# PRegulator.net
KiCad netlist of a schematic drawn in Altium Designer
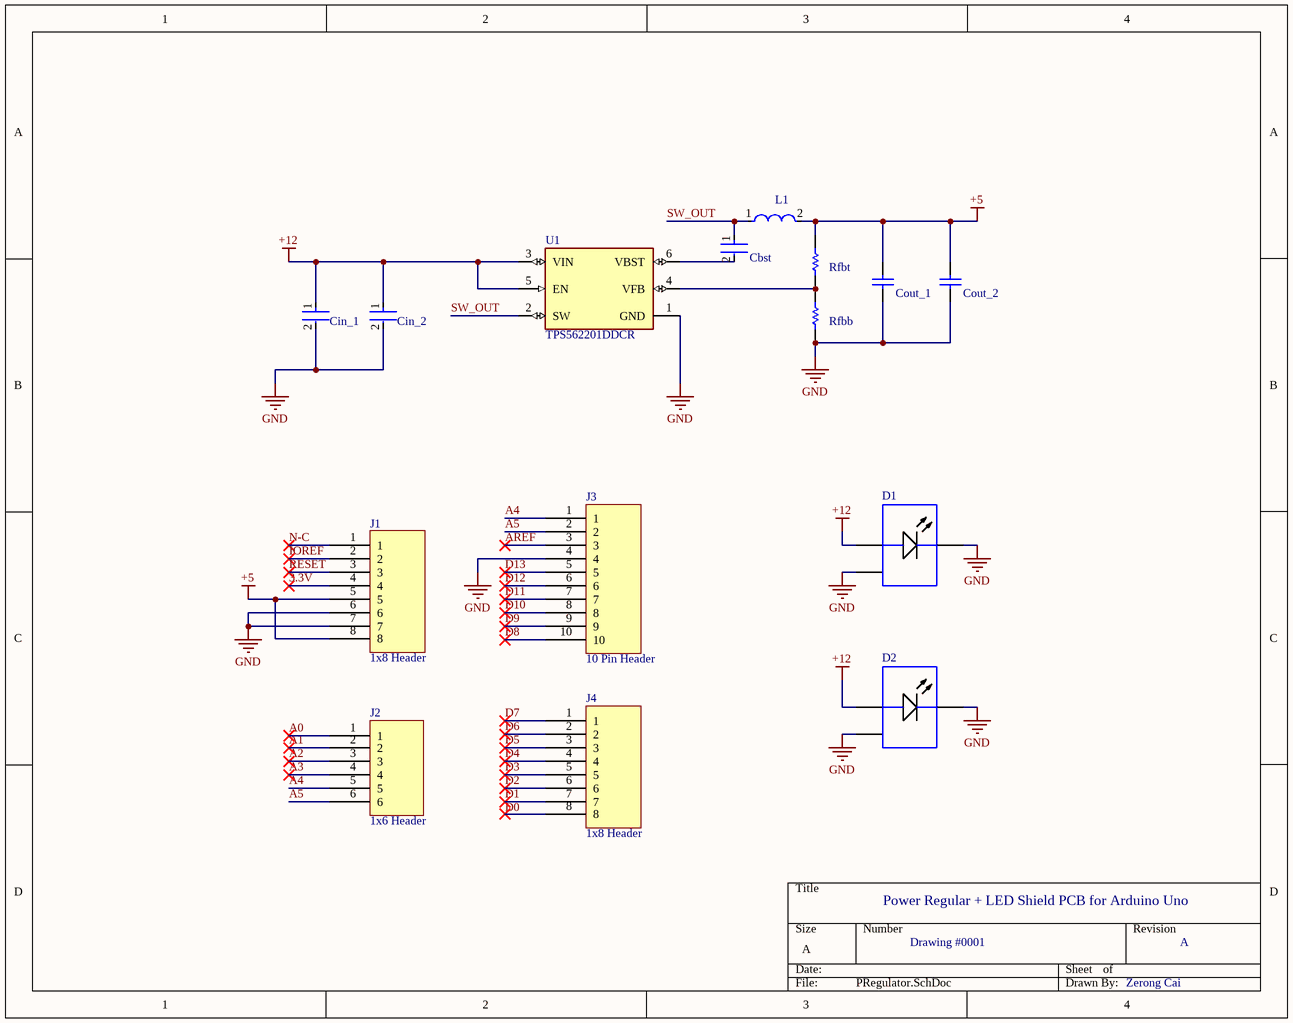
[diagram p0: PRegulator.SchDoc]

(export (version "E")
  (design (tool "Eeschema 10.0.6"))
  (components
    (comp (ref "Cbst")
      (value "08053C104KAT2A")
      (footprint "FP-0805-L_2_01_0_2-W_1_25-IPC_C")
      (description "General Purpose Ceramic Capacitor, 0805, 100nF, 10%, X7R, 0.15, 25V")
      (fields (field (name "TOLERANCE") "10%") (field (name "VOLTAGE") "25V"))
      (libsource (lib "Altium Content Vault") (part "02cd4be3c70576c341d710602a673aa"))
    )
    (comp (ref "Cin_1")
      (value "C2012X5R1V106K125AC")
      (footprint "FP-C2012-125-0_2-IPC_B")
      (description "Multilayer Ceramic Capacitors 10μF ±10% 35V X5R SMD 0805")
      (fields (field (name "TOLERANCE") "10%"))
      (libsource (lib "Altium Content Vault") (part "b4654b650e69147ec39a6b967a45e02"))
    )
    (comp (ref "Cin_2")
      (value "C2012X5R1V106K125AC")
      (footprint "FP-C2012-125-0_2-IPC_B")
      (description "Multilayer Ceramic Capacitors 10μF ±10% 35V X5R SMD 0805")
      (fields (field (name "TOLERANCE") "10%"))
      (libsource (lib "Altium Content Vault") (part "b4654b650e69147ec39a6b967a45e02"))
    )
    (comp (ref "Cout_1")
      (value "C1608X5R1A226M080AC")
      (footprint "CAPC1608X100X20ML10")
      (description "Chip Capacitor, 22 uF, +/- 20%, 10 V, -55 to 85 degC, 0603 (1608 Metric), RoHS, Tape and Reel")
      (fields (field (name "MANUFACTURER") "TDK") (field (name "TOLERANCE") "±20%"))
      (libsource (lib "Altium Content Vault") (part "CAP-NP-2"))
    )
    (comp (ref "Cout_2")
      (value "C1608X5R1A226M080AC")
      (footprint "CAPC1608X100X20ML10")
      (description "Chip Capacitor, 22 uF, +/- 20%, 10 V, -55 to 85 degC, 0603 (1608 Metric), RoHS, Tape and Reel")
      (fields (field (name "MANUFACTURER") "TDK") (field (name "TOLERANCE") "±20%"))
      (libsource (lib "Altium Content Vault") (part "CAP-NP-2"))
    )
    (comp (ref "D1")
      (value "MKRAWT-00-0000-0D0HG235H")
      (footprint "CREE-MK-R-2_V")
      (description "LED, White, 12 V, 2-Pin SMD, RoHS, Tape and Reel")
      (libsource (lib "Altium Content Vault") (part "LED_WHITE-3"))
    )
    (comp (ref "D2")
      (value "MKRAWT-00-0000-0D0HG235H")
      (footprint "CREE-MK-R-2_V")
      (description "LED, White, 12 V, 2-Pin SMD, RoHS, Tape and Reel")
      (libsource (lib "Altium Content Vault") (part "LED_WHITE-3"))
    )
    (comp (ref "J1")
      (value "1x8 Header")
      (footprint "1x8Header")
      (libsource (lib "1x8_Header") (part "8 Pin Header"))
    )
    (comp (ref "J2")
      (value "1x6 Header")
      (footprint "1x6Header")
      (description "SSQ-106-03-T-S")
      (libsource (lib "1x6_Header") (part "6 Pin Header"))
    )
    (comp (ref "J3")
      (value "10 Pin Header")
      (footprint "10 Pin Header-Footprint-1")
      (description "SPQ-110-03-T-S")
      (libsource (lib "University of California, Riverside") (part "10 Pin Header"))
    )
    (comp (ref "J4")
      (value "1x8 Header")
      (footprint "1x8Header")
      (libsource (lib "1x8_Header") (part "8 Pin Header"))
    )
    (comp (ref "L1")
      (value "NRS8030T3R3MJGJ")
      (footprint "FP-NRS8030-MFG")
      (description "Inductor Power Shielded Wirewound 3.3uH 20% 100KHz Ferrite 4.2A 24.7mΩ DCR T/R")
      (fields (field (name "TOLERANCE") "20%"))
      (libsource (lib "Altium Content Vault") (part "725321dda6339637d4d059423bc1c3c"))
    )
    (comp (ref "Rfbb")
      (value "ERJ2RKF1002X")
      (footprint "RESC1005X40X25LL05T05")
      (description "Chip Resistor, 10 KOhm, +/- 1%, 0.1 W, -55 to 155 degC, 0402 (1005 Metric), RoHS, Tape and Reel")
      (fields (field (name "TOLERANCE") "1%") (field (name "MANUFACTURER") "Panasonic"))
      (libsource (lib "Altium Content Vault") (part "RES-2"))
    )
    (comp (ref "Rfbt")
      (value "CRCW020156K2FNED")
      (footprint "RESC0603X28X15NL05T05")
      (description "56.2kOhm, Tolerance = 1.0%, Power = 50 mW")
      (fields (field (name "MANUFACTURER") "Vishay Dale"))
      (libsource (lib "Altium Content Vault") (part "RES"))
    )
    (comp (ref "U1")
      (value "TPS562201DDCR")
      (footprint "FP-DDC0006A-IPC_C")
      (description "IC REG BUCK ADJ 2A TSOT23-6")
      (libsource (lib "Altium Content Vault") (part "957e164956730ea4bf6293280af19fc"))
    )
  )
  (nets
    (net (code "1") (name "+5") (class "Default")
      (node (ref "Cout_1") (pin "2") (pinfunction "2_2") (pintype "passive"))
      (node (ref "Cout_2") (pin "2") (pinfunction "2_2") (pintype "passive"))
      (node (ref "J1") (pin "5") (pinfunction "5_5") (pintype "passive"))
      (node (ref "J1") (pin "8") (pinfunction "8_8") (pintype "passive"))
      (node (ref "L1") (pin "2") (pinfunction "2_2") (pintype "passive"))
      (node (ref "Rfbt") (pin "2") (pinfunction "2_2") (pintype "passive"))
    )
    (net (code "2") (name "+12") (class "Default")
      (node (ref "Cin_1") (pin "1") (pinfunction "1_1") (pintype "passive"))
      (node (ref "Cin_2") (pin "1") (pinfunction "1_1") (pintype "passive"))
      (node (ref "D1") (pin "1") (pinfunction "A_1") (pintype "passive"))
      (node (ref "D2") (pin "1") (pinfunction "A_1") (pintype "passive"))
      (node (ref "U1") (pin "3") (pinfunction "VIN_3") (pintype "bidirectional"))
      (node (ref "U1") (pin "5") (pinfunction "EN_5") (pintype "input"))
    )
    (net (code "3") (name "/3.3V") (class "Default")
      (node (ref "J1") (pin "4") (pinfunction "4_4") (pintype "passive+no_connect"))
    )
    (net (code "4") (name "/A0") (class "Default")
      (node (ref "J2") (pin "1") (pinfunction "1_1") (pintype "passive+no_connect"))
    )
    (net (code "5") (name "/A1") (class "Default")
      (node (ref "J2") (pin "2") (pinfunction "2_2") (pintype "passive+no_connect"))
    )
    (net (code "6") (name "/A2") (class "Default")
      (node (ref "J2") (pin "3") (pinfunction "3_3") (pintype "passive+no_connect"))
    )
    (net (code "7") (name "/A3") (class "Default")
      (node (ref "J2") (pin "4") (pinfunction "4_4") (pintype "passive+no_connect"))
    )
    (net (code "8") (name "/A4") (class "Default")
      (node (ref "J2") (pin "5") (pinfunction "5_5") (pintype "passive"))
      (node (ref "J3") (pin "1") (pinfunction "1_1") (pintype "passive"))
    )
    (net (code "9") (name "/A5") (class "Default")
      (node (ref "J2") (pin "6") (pinfunction "6_6") (pintype "passive"))
      (node (ref "J3") (pin "2") (pinfunction "2_2") (pintype "passive"))
    )
    (net (code "10") (name "/AREF") (class "Default")
      (node (ref "J3") (pin "3") (pinfunction "3_3") (pintype "passive+no_connect"))
    )
    (net (code "12") (name "/D1") (class "Default")
      (node (ref "J4") (pin "7") (pinfunction "7_7") (pintype "passive+no_connect"))
    )
    (net (code "13") (name "/D2") (class "Default")
      (node (ref "J4") (pin "6") (pinfunction "6_6") (pintype "passive+no_connect"))
    )
    (net (code "14") (name "/D3") (class "Default")
      (node (ref "J4") (pin "5") (pinfunction "5_5") (pintype "passive+no_connect"))
    )
    (net (code "15") (name "/D4") (class "Default")
      (node (ref "J4") (pin "4") (pinfunction "4_4") (pintype "passive+no_connect"))
    )
    (net (code "16") (name "/D5") (class "Default")
      (node (ref "J4") (pin "3") (pinfunction "3_3") (pintype "passive+no_connect"))
    )
    (net (code "17") (name "/D6") (class "Default")
      (node (ref "J4") (pin "2") (pinfunction "2_2") (pintype "passive+no_connect"))
    )
    (net (code "18") (name "/D7") (class "Default")
      (node (ref "J4") (pin "1") (pinfunction "1_1") (pintype "passive+no_connect"))
    )
    (net (code "19") (name "/D8") (class "Default")
      (node (ref "J3") (pin "10") (pinfunction "10_10") (pintype "passive+no_connect"))
    )
    (net (code "20") (name "/D9") (class "Default")
      (node (ref "J3") (pin "9") (pinfunction "9_9") (pintype "passive+no_connect"))
    )
    (net (code "21") (name "/D10") (class "Default")
      (node (ref "J3") (pin "8") (pinfunction "8_8") (pintype "passive+no_connect"))
    )
    (net (code "22") (name "/D11") (class "Default")
      (node (ref "J3") (pin "7") (pinfunction "7_7") (pintype "passive+no_connect"))
    )
    (net (code "23") (name "/D12") (class "Default")
      (node (ref "J3") (pin "6") (pinfunction "6_6") (pintype "passive+no_connect"))
    )
    (net (code "24") (name "/D13") (class "Default")
      (node (ref "J3") (pin "5") (pinfunction "5_5") (pintype "passive+no_connect"))
    )
    (net (code "25") (name "/IOREF") (class "Default")
      (node (ref "J1") (pin "2") (pinfunction "2_2") (pintype "passive+no_connect"))
    )
    (net (code "26") (name "/N-C") (class "Default")
      (node (ref "J1") (pin "1") (pinfunction "1_1") (pintype "passive+no_connect"))
    )
    (net (code "27") (name "/RESET") (class "Default")
      (node (ref "J1") (pin "3") (pinfunction "3_3") (pintype "passive+no_connect"))
    )
    (net (code "28") (name "/SW_OUT") (class "Default")
      (node (ref "Cbst") (pin "1") (pinfunction "1_1") (pintype "passive"))
      (node (ref "L1") (pin "1") (pinfunction "1_1") (pintype "passive"))
      (node (ref "U1") (pin "2") (pinfunction "SW_2") (pintype "bidirectional"))
    )
    (net (code "29") (name "GND") (class "Default")
      (node (ref "Cin_1") (pin "2") (pinfunction "2_2") (pintype "passive"))
      (node (ref "Cin_2") (pin "2") (pinfunction "2_2") (pintype "passive"))
      (node (ref "Cout_1") (pin "1") (pinfunction "1_1") (pintype "passive"))
      (node (ref "Cout_2") (pin "1") (pinfunction "1_1") (pintype "passive"))
      (node (ref "D1") (pin "2") (pinfunction "K_2") (pintype "passive"))
      (node (ref "D1") (pin "3") (pinfunction "EP_3") (pintype "passive"))
      (node (ref "D2") (pin "2") (pinfunction "K_2") (pintype "passive"))
      (node (ref "D2") (pin "3") (pinfunction "EP_3") (pintype "passive"))
      (node (ref "J1") (pin "6") (pinfunction "6_6") (pintype "passive"))
      (node (ref "J1") (pin "7") (pinfunction "7_7") (pintype "passive"))
      (node (ref "J3") (pin "4") (pinfunction "4_4") (pintype "passive"))
      (node (ref "Rfbb") (pin "1") (pinfunction "1_1") (pintype "passive"))
      (node (ref "U1") (pin "1") (pinfunction "GND_1") (pintype "power_in"))
    )
    (net (code "30") (name "Net-(U1-VBST)") (class "Default")
      (node (ref "Cbst") (pin "2") (pinfunction "2_2") (pintype "passive"))
      (node (ref "U1") (pin "6") (pinfunction "VBST_6") (pintype "bidirectional"))
    )
    (net (code "31") (name "Net-(U1-VFB)") (class "Default")
      (node (ref "Rfbb") (pin "2") (pinfunction "2_2") (pintype "passive"))
      (node (ref "Rfbt") (pin "1") (pinfunction "1_1") (pintype "passive"))
      (node (ref "U1") (pin "4") (pinfunction "VFB_4") (pintype "bidirectional"))
    )
    (net (code "32") (name "unconnected-(J4-Pad8)") (class "Default")
      (node (ref "J4") (pin "8") (pinfunction "8_8") (pintype "passive+no_connect"))
    )
  )
)
